# Logger_ver1_0_0.net
KiCad netlist of a schematic drawn in EAGLE
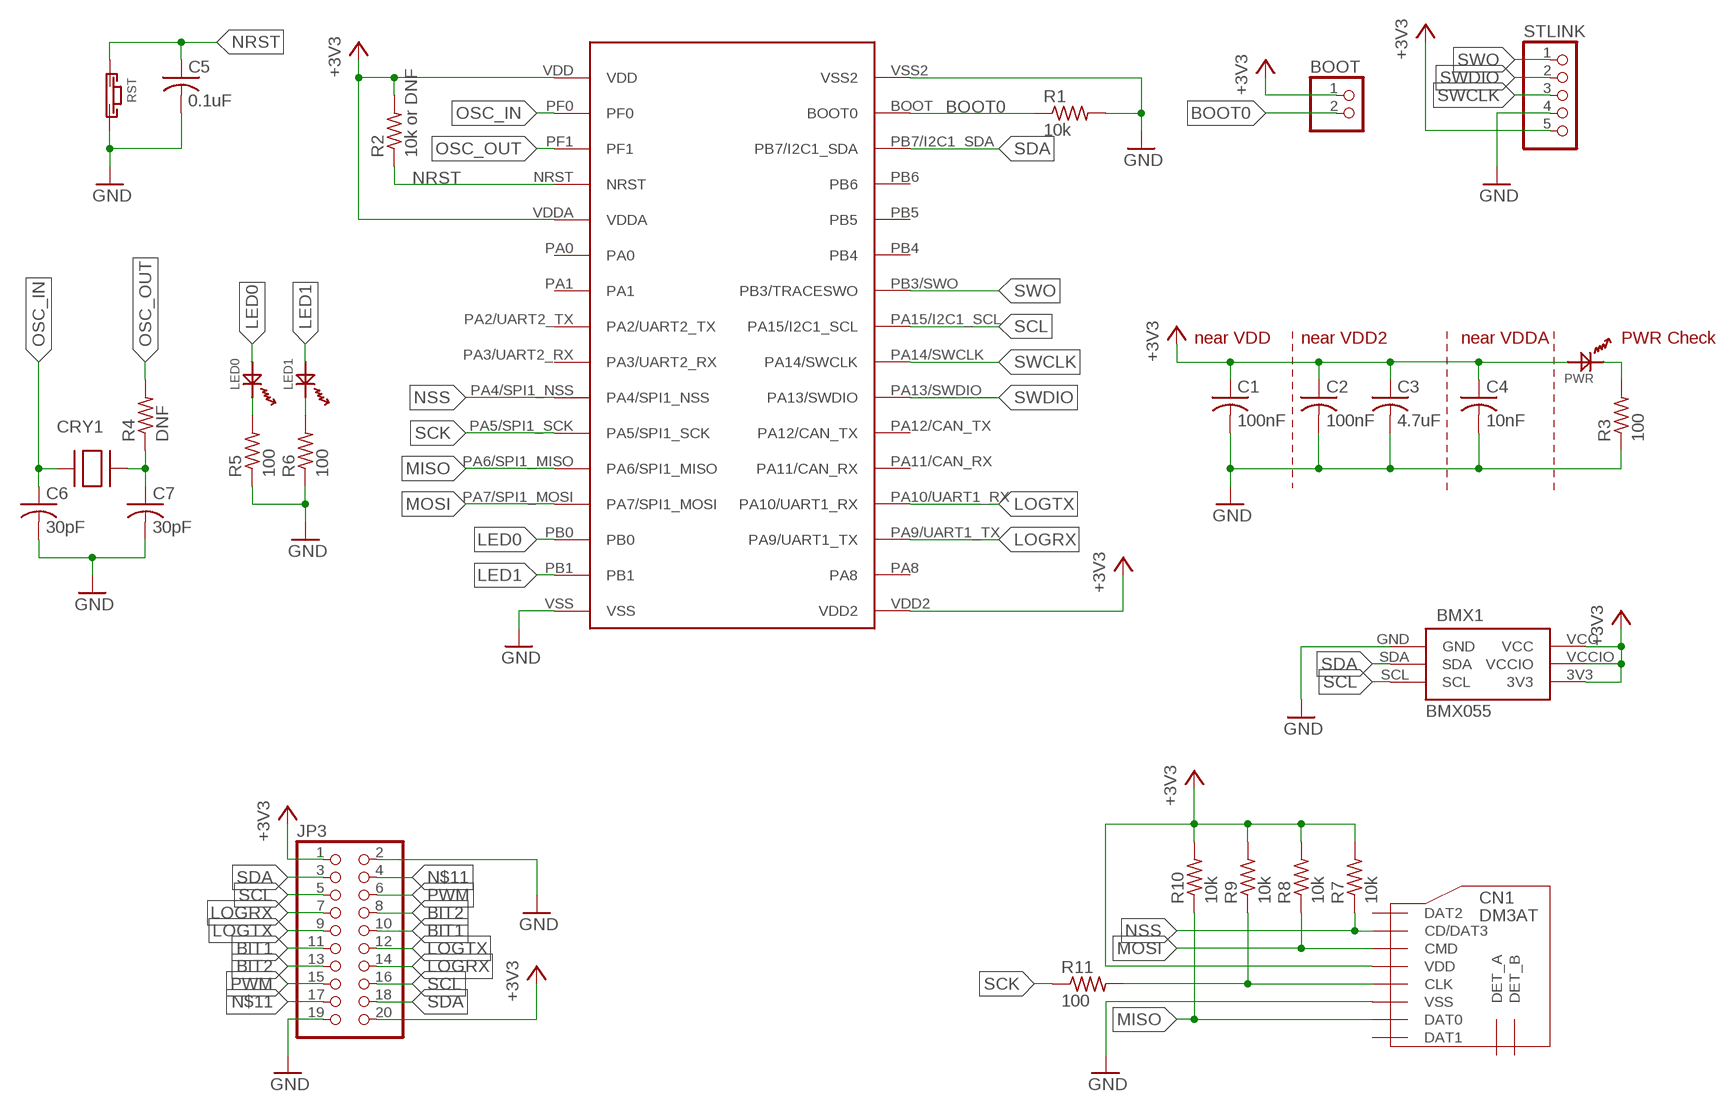
[diagram p0: schematic, sheet 1]

(export (version "E")
  (design (tool "Eeschema 10.0.6"))
  (components
    (comp (ref "BMX1")
      (value "BMX055")
      (footprint "eagle-import:BMX055")
      (libsource (lib "eagle-import") (part "BMX055"))
    )
    (comp (ref "BOOT")
      (value "PINHD-1X2/90")
      (footprint "eagle-import:1X02_90")
      (libsource (lib "eagle-import") (part "PINHD-1X2/90"))
    )
    (comp (ref "C1")
      (value "100nF")
      (footprint "eagle-import:C1608")
      (libsource (lib "eagle-import") (part "C-USC1608"))
    )
    (comp (ref "C2")
      (value "100nF")
      (footprint "eagle-import:C1608")
      (libsource (lib "eagle-import") (part "C-USC1608"))
    )
    (comp (ref "C3")
      (value "4.7uF")
      (footprint "eagle-import:C1608")
      (libsource (lib "eagle-import") (part "C-USC1608"))
    )
    (comp (ref "C4")
      (value "10nF")
      (footprint "eagle-import:C1608")
      (libsource (lib "eagle-import") (part "C-USC1608"))
    )
    (comp (ref "C5")
      (value "0.1uF")
      (footprint "eagle-import:C1608")
      (libsource (lib "eagle-import") (part "C-USC1608"))
    )
    (comp (ref "C6")
      (value "30pF")
      (footprint "eagle-import:C1608")
      (libsource (lib "eagle-import") (part "C-USC1608"))
    )
    (comp (ref "C7")
      (value "30pF")
      (footprint "eagle-import:C1608")
      (libsource (lib "eagle-import") (part "C-USC1608"))
    )
    (comp (ref "CN1")
      (value "DM3AT")
      (footprint "eagle-import:DM3AT")
      (libsource (lib "eagle-import") (part "DM3AT"))
    )
    (comp (ref "CRY1")
      (value "8MHZ")
      (footprint "eagle-import:CRYSTAL")
      (libsource (lib "eagle-import") (part "8MHZ"))
    )
    (comp (ref "JP3")
      (value "PINHD-2X10/90")
      (footprint "eagle-import:2X10_90")
      (libsource (lib "eagle-import") (part "PINHD-2X10/90"))
    )
    (comp (ref "LED0")
      (value "OSXX1608C1A")
      (footprint "eagle-import:OSXX1608C1A")
      (libsource (lib "eagle-import") (part "OSXX1608C1A"))
    )
    (comp (ref "LED1")
      (value "OSXX1608C1A")
      (footprint "eagle-import:OSXX1608C1A")
      (libsource (lib "eagle-import") (part "OSXX1608C1A"))
    )
    (comp (ref "PWR")
      (value "OSXX1608C1A")
      (footprint "eagle-import:OSXX1608C1A")
      (libsource (lib "eagle-import") (part "OSXX1608C1A"))
    )
    (comp (ref "R1")
      (value "10k")
      (footprint "eagle-import:R0603")
      (libsource (lib "eagle-import") (part "R-US_R0603"))
    )
    (comp (ref "R2")
      (value "10k or DNF")
      (footprint "eagle-import:R0603")
      (libsource (lib "eagle-import") (part "R-US_R0603"))
    )
    (comp (ref "R3")
      (value "100")
      (footprint "eagle-import:R0603")
      (libsource (lib "eagle-import") (part "R-US_R0603"))
    )
    (comp (ref "R4")
      (value "DNF")
      (footprint "eagle-import:R0603")
      (libsource (lib "eagle-import") (part "R-US_R0603"))
    )
    (comp (ref "R5")
      (value "100")
      (footprint "eagle-import:R0603")
      (libsource (lib "eagle-import") (part "R-US_R0603"))
    )
    (comp (ref "R6")
      (value "100")
      (footprint "eagle-import:R0603")
      (libsource (lib "eagle-import") (part "R-US_R0603"))
    )
    (comp (ref "R7")
      (value "10k")
      (footprint "eagle-import:R0603")
      (libsource (lib "eagle-import") (part "R-US_R0603"))
    )
    (comp (ref "R8")
      (value "10k")
      (footprint "eagle-import:R0603")
      (libsource (lib "eagle-import") (part "R-US_R0603"))
    )
    (comp (ref "R9")
      (value "10k")
      (footprint "eagle-import:R0603")
      (libsource (lib "eagle-import") (part "R-US_R0603"))
    )
    (comp (ref "R10")
      (value "10k")
      (footprint "eagle-import:R0603")
      (libsource (lib "eagle-import") (part "R-US_R0603"))
    )
    (comp (ref "R11")
      (value "100")
      (footprint "eagle-import:R0603")
      (libsource (lib "eagle-import") (part "R-US_R0603"))
    )
    (comp (ref "RST")
      (value "TVAF06-A020B-R")
      (footprint "eagle-import:TVAF06-A020B-R")
      (libsource (lib "eagle-import") (part "TVAF06-A020B-R"))
    )
    (comp (ref "STLINK")
      (value "PINHD-1X5/90")
      (footprint "eagle-import:1X05_90")
      (libsource (lib "eagle-import") (part "PINHD-1X5/90"))
    )
    (comp (ref "U$1")
      (value "STM32F303K8")
      (footprint "eagle-import:STM32F303K8")
      (libsource (lib "eagle-import") (part "STM32F303K8"))
    )
  )
  (nets
    (net (code "1") (name "+3V3") (class "Default")
      (node (ref "BMX1") (pin "3V3") (pinfunction "3V3_3V3") (pintype "power_in"))
      (node (ref "BMX1") (pin "VCC") (pinfunction "VCC_VCC") (pintype "power_in"))
      (node (ref "BMX1") (pin "VCCIO") (pinfunction "VCCIO_VCCIO") (pintype "power_in"))
      (node (ref "BOOT") (pin "1") (pinfunction "1_1") (pintype "passive"))
      (node (ref "C1") (pin "1") (pinfunction "1_1") (pintype "passive"))
      (node (ref "C2") (pin "1") (pinfunction "1_1") (pintype "passive"))
      (node (ref "C3") (pin "1") (pinfunction "1_1") (pintype "passive"))
      (node (ref "C4") (pin "1") (pinfunction "1_1") (pintype "passive"))
      (node (ref "CN1") (pin "VDD") (pinfunction "VDD_VDD") (pintype "bidirectional"))
      (node (ref "JP3") (pin "1") (pinfunction "1_1") (pintype "passive"))
      (node (ref "JP3") (pin "20") (pinfunction "20_20") (pintype "passive"))
      (node (ref "PWR") (pin "AN") (pinfunction "AN_AN") (pintype "bidirectional"))
      (node (ref "R10") (pin "2") (pinfunction "2_2") (pintype "passive"))
      (node (ref "R2") (pin "2") (pinfunction "2_2") (pintype "passive"))
      (node (ref "R7") (pin "2") (pinfunction "2_2") (pintype "passive"))
      (node (ref "R8") (pin "2") (pinfunction "2_2") (pintype "passive"))
      (node (ref "R9") (pin "2") (pinfunction "2_2") (pintype "passive"))
      (node (ref "STLINK") (pin "5") (pinfunction "5_5") (pintype "passive"))
      (node (ref "U$1") (pin "VDD") (pinfunction "VDD_VDD") (pintype "power_in"))
      (node (ref "U$1") (pin "VDD2") (pinfunction "VDD2_VDD2") (pintype "power_in"))
      (node (ref "U$1") (pin "VDDA") (pinfunction "VDDA_VDDA") (pintype "power_in"))
    )
    (net (code "2") (name "BIT1") (class "Default")
      (node (ref "JP3") (pin "10") (pinfunction "10_10") (pintype "passive"))
      (node (ref "JP3") (pin "11") (pinfunction "11_11") (pintype "passive"))
    )
    (net (code "3") (name "BIT2") (class "Default")
      (node (ref "JP3") (pin "13") (pinfunction "13_13") (pintype "passive"))
      (node (ref "JP3") (pin "8") (pinfunction "8_8") (pintype "passive"))
    )
    (net (code "4") (name "BOOT0") (class "Default")
      (node (ref "BOOT") (pin "2") (pinfunction "2_2") (pintype "passive"))
      (node (ref "R1") (pin "1") (pinfunction "1_1") (pintype "passive"))
      (node (ref "U$1") (pin "BOOT") (pinfunction "BOOT0_BOOT") (pintype "bidirectional"))
    )
    (net (code "5") (name "GND") (class "Default")
      (node (ref "BMX1") (pin "GND") (pinfunction "GND_GND") (pintype "power_in"))
      (node (ref "C1") (pin "2") (pinfunction "2_2") (pintype "passive"))
      (node (ref "C2") (pin "2") (pinfunction "2_2") (pintype "passive"))
      (node (ref "C3") (pin "2") (pinfunction "2_2") (pintype "passive"))
      (node (ref "C4") (pin "2") (pinfunction "2_2") (pintype "passive"))
      (node (ref "C5") (pin "2") (pinfunction "2_2") (pintype "passive"))
      (node (ref "C6") (pin "2") (pinfunction "2_2") (pintype "passive"))
      (node (ref "C7") (pin "2") (pinfunction "2_2") (pintype "passive"))
      (node (ref "CN1") (pin "VSS") (pinfunction "VSS_VSS") (pintype "bidirectional"))
      (node (ref "JP3") (pin "19") (pinfunction "19_19") (pintype "passive"))
      (node (ref "JP3") (pin "2") (pinfunction "2_2") (pintype "passive"))
      (node (ref "R1") (pin "2") (pinfunction "2_2") (pintype "passive"))
      (node (ref "R3") (pin "1") (pinfunction "1_1") (pintype "passive"))
      (node (ref "R5") (pin "1") (pinfunction "1_1") (pintype "passive"))
      (node (ref "R6") (pin "1") (pinfunction "1_1") (pintype "passive"))
      (node (ref "RST") (pin "P$2") (pinfunction "P$2_P$2") (pintype "bidirectional"))
      (node (ref "STLINK") (pin "4") (pinfunction "4_4") (pintype "passive"))
      (node (ref "U$1") (pin "VSS") (pinfunction "VSS_VSS") (pintype "power_in"))
      (node (ref "U$1") (pin "VSS2") (pinfunction "VSS2_VSS2") (pintype "power_in"))
    )
    (net (code "6") (name "LED0") (class "Default")
      (node (ref "LED0") (pin "AN") (pinfunction "AN_AN") (pintype "bidirectional"))
      (node (ref "U$1") (pin "PB0") (pinfunction "PB0_PB0") (pintype "bidirectional"))
    )
    (net (code "7") (name "LED1") (class "Default")
      (node (ref "LED1") (pin "AN") (pinfunction "AN_AN") (pintype "bidirectional"))
      (node (ref "U$1") (pin "PB1") (pinfunction "PB1_PB1") (pintype "bidirectional"))
    )
    (net (code "8") (name "LOGRX") (class "Default")
      (node (ref "JP3") (pin "14") (pinfunction "14_14") (pintype "passive"))
      (node (ref "JP3") (pin "7") (pinfunction "7_7") (pintype "passive"))
      (node (ref "U$1") (pin "PA9/UART1_TX") (pinfunction "PA9/UART1_TX_PA9/UART1_TX") (pintype "bidirectional"))
    )
    (net (code "9") (name "LOGTX") (class "Default")
      (node (ref "JP3") (pin "12") (pinfunction "12_12") (pintype "passive"))
      (node (ref "JP3") (pin "9") (pinfunction "9_9") (pintype "passive"))
      (node (ref "U$1") (pin "PA10/UART1_RX") (pinfunction "PA10/UART1_RX_PA10/UART1_RX") (pintype "bidirectional"))
    )
    (net (code "10") (name "MISO") (class "Default")
      (node (ref "CN1") (pin "DAT0") (pinfunction "DAT0_DAT0") (pintype "bidirectional"))
      (node (ref "R10") (pin "1") (pinfunction "1_1") (pintype "passive"))
      (node (ref "U$1") (pin "PA6/SPI1_MISO") (pinfunction "PA6/SPI1_MISO_PA6/SPI1_MISO") (pintype "bidirectional"))
    )
    (net (code "11") (name "MOSI") (class "Default")
      (node (ref "CN1") (pin "CMD") (pinfunction "CMD_CMD") (pintype "bidirectional"))
      (node (ref "R8") (pin "1") (pinfunction "1_1") (pintype "passive"))
      (node (ref "U$1") (pin "PA7/SPI1_MOSI") (pinfunction "PA7/SPI1_MOSI_PA7/SPI1_MOSI") (pintype "bidirectional"))
    )
    (net (code "12") (name "N$11") (class "Default")
      (node (ref "JP3") (pin "17") (pinfunction "17_17") (pintype "passive"))
      (node (ref "JP3") (pin "4") (pinfunction "4_4") (pintype "passive"))
    )
    (net (code "13") (name "NRST") (class "Default")
      (node (ref "C5") (pin "1") (pinfunction "1_1") (pintype "passive"))
      (node (ref "R2") (pin "1") (pinfunction "1_1") (pintype "passive"))
      (node (ref "RST") (pin "P$1") (pinfunction "P$1_P$1") (pintype "bidirectional"))
      (node (ref "U$1") (pin "NRST") (pinfunction "NRST_NRST") (pintype "bidirectional"))
    )
    (net (code "14") (name "NSS") (class "Default")
      (node (ref "CN1") (pin "CD/DAT3") (pinfunction "CD/DAT3_CD/DAT3") (pintype "bidirectional"))
      (node (ref "R7") (pin "1") (pinfunction "1_1") (pintype "passive"))
      (node (ref "U$1") (pin "PA4/SPI1_NSS") (pinfunction "PA4/SPI1_NSS_PA4/SPI1_NSS") (pintype "bidirectional"))
    )
    (net (code "15") (name "Net-(C7-Pad1)") (class "Default")
      (node (ref "C7") (pin "1") (pinfunction "1_1") (pintype "passive"))
      (node (ref "CRY1") (pin "P$2") (pinfunction "P$2_P$2") (pintype "bidirectional"))
      (node (ref "R4") (pin "1") (pinfunction "1_1") (pintype "passive"))
    )
    (net (code "16") (name "Net-(CN1-PadCLK)") (class "Default")
      (node (ref "CN1") (pin "CLK") (pinfunction "CLK_CLK") (pintype "bidirectional"))
      (node (ref "R11") (pin "2") (pinfunction "2_2") (pintype "passive"))
      (node (ref "R9") (pin "1") (pinfunction "1_1") (pintype "passive"))
    )
    (net (code "17") (name "Net-(LED0-PadCT)") (class "Default")
      (node (ref "LED0") (pin "CT") (pinfunction "CT_CT") (pintype "bidirectional"))
      (node (ref "R5") (pin "2") (pinfunction "2_2") (pintype "passive"))
    )
    (net (code "18") (name "Net-(LED1-PadCT)") (class "Default")
      (node (ref "LED1") (pin "CT") (pinfunction "CT_CT") (pintype "bidirectional"))
      (node (ref "R6") (pin "2") (pinfunction "2_2") (pintype "passive"))
    )
    (net (code "19") (name "Net-(PWR-PadCT)") (class "Default")
      (node (ref "PWR") (pin "CT") (pinfunction "CT_CT") (pintype "bidirectional"))
      (node (ref "R3") (pin "2") (pinfunction "2_2") (pintype "passive"))
    )
    (net (code "20") (name "OSC_IN") (class "Default")
      (node (ref "C6") (pin "1") (pinfunction "1_1") (pintype "passive"))
      (node (ref "CRY1") (pin "P$1") (pinfunction "P$1_P$1") (pintype "bidirectional"))
      (node (ref "U$1") (pin "PF0") (pinfunction "PF0_PF0") (pintype "bidirectional"))
    )
    (net (code "21") (name "OSC_OUT") (class "Default")
      (node (ref "R4") (pin "2") (pinfunction "2_2") (pintype "passive"))
      (node (ref "U$1") (pin "PF1") (pinfunction "PF1_PF1") (pintype "bidirectional"))
    )
    (net (code "22") (name "PWM") (class "Default")
      (node (ref "JP3") (pin "15") (pinfunction "15_15") (pintype "passive"))
      (node (ref "JP3") (pin "6") (pinfunction "6_6") (pintype "passive"))
    )
    (net (code "23") (name "SCK") (class "Default")
      (node (ref "R11") (pin "1") (pinfunction "1_1") (pintype "passive"))
      (node (ref "U$1") (pin "PA5/SPI1_SCK") (pinfunction "PA5/SPI1_SCK_PA5/SPI1_SCK") (pintype "bidirectional"))
    )
    (net (code "24") (name "SCL") (class "Default")
      (node (ref "BMX1") (pin "SCL") (pinfunction "SCL_SCL") (pintype "bidirectional"))
      (node (ref "JP3") (pin "16") (pinfunction "16_16") (pintype "passive"))
      (node (ref "JP3") (pin "5") (pinfunction "5_5") (pintype "passive"))
      (node (ref "U$1") (pin "PA15/I2C1_SCL") (pinfunction "PA15/I2C1_SCL_PA15/I2C1_SCL") (pintype "bidirectional"))
    )
    (net (code "25") (name "SDA") (class "Default")
      (node (ref "BMX1") (pin "SDA") (pinfunction "SDA_SDA") (pintype "bidirectional"))
      (node (ref "JP3") (pin "18") (pinfunction "18_18") (pintype "passive"))
      (node (ref "JP3") (pin "3") (pinfunction "3_3") (pintype "passive"))
      (node (ref "U$1") (pin "PB7/I2C1_SDA") (pinfunction "PB7/I2C1_SDA_PB7/I2C1_SDA") (pintype "bidirectional"))
    )
    (net (code "26") (name "SWCLK") (class "Default")
      (node (ref "STLINK") (pin "3") (pinfunction "3_3") (pintype "passive"))
      (node (ref "U$1") (pin "PA14/SWCLK") (pinfunction "PA14/SWCLK_PA14/SWCLK") (pintype "bidirectional"))
    )
    (net (code "27") (name "SWDIO") (class "Default")
      (node (ref "STLINK") (pin "2") (pinfunction "2_2") (pintype "passive"))
      (node (ref "U$1") (pin "PA13/SWDIO") (pinfunction "PA13/SWDIO_PA13/SWDIO") (pintype "bidirectional"))
    )
    (net (code "28") (name "SWO") (class "Default")
      (node (ref "STLINK") (pin "1") (pinfunction "1_1") (pintype "passive"))
      (node (ref "U$1") (pin "PB3/SWO") (pinfunction "PB3/TRACESWO_PB3/SWO") (pintype "bidirectional"))
    )
    (net (code "29") (name "unconnected-(CN1-PadDAT1)") (class "Default")
      (node (ref "CN1") (pin "DAT1") (pinfunction "DAT1_DAT1") (pintype "bidirectional"))
    )
    (net (code "30") (name "unconnected-(CN1-PadDAT2)") (class "Default")
      (node (ref "CN1") (pin "DAT2") (pinfunction "DAT2_DAT2") (pintype "bidirectional"))
    )
    (net (code "31") (name "unconnected-(CN1-PadDET_A)") (class "Default")
      (node (ref "CN1") (pin "DET_A") (pinfunction "DET_A_DET_A") (pintype "bidirectional"))
    )
    (net (code "32") (name "unconnected-(CN1-PadDET_B)") (class "Default")
      (node (ref "CN1") (pin "DET_B") (pinfunction "DET_B_DET_B") (pintype "bidirectional"))
    )
    (net (code "33") (name "unconnected-(U$1-PadPA0)") (class "Default")
      (node (ref "U$1") (pin "PA0") (pinfunction "PA0_PA0") (pintype "bidirectional"))
    )
    (net (code "34") (name "unconnected-(U$1-PadPA1)") (class "Default")
      (node (ref "U$1") (pin "PA1") (pinfunction "PA1_PA1") (pintype "bidirectional"))
    )
    (net (code "35") (name "unconnected-(U$1-PadPA2{slash}UART2_TX)") (class "Default")
      (node (ref "U$1") (pin "PA2/UART2_TX") (pinfunction "PA2/UART2_TX_PA2/UART2_TX") (pintype "bidirectional"))
    )
    (net (code "36") (name "unconnected-(U$1-PadPA3{slash}UART2_RX)") (class "Default")
      (node (ref "U$1") (pin "PA3/UART2_RX") (pinfunction "PA3/UART2_RX_PA3/UART2_RX") (pintype "bidirectional"))
    )
    (net (code "37") (name "unconnected-(U$1-PadPA8)") (class "Default")
      (node (ref "U$1") (pin "PA8") (pinfunction "PA8_PA8") (pintype "bidirectional"))
    )
    (net (code "38") (name "unconnected-(U$1-PadPA11{slash}CAN_RX)") (class "Default")
      (node (ref "U$1") (pin "PA11/CAN_RX") (pinfunction "PA11/CAN_RX_PA11/CAN_RX") (pintype "bidirectional"))
    )
    (net (code "39") (name "unconnected-(U$1-PadPA12{slash}CAN_TX)") (class "Default")
      (node (ref "U$1") (pin "PA12/CAN_TX") (pinfunction "PA12/CAN_TX_PA12/CAN_TX") (pintype "bidirectional"))
    )
    (net (code "40") (name "unconnected-(U$1-PadPB4)") (class "Default")
      (node (ref "U$1") (pin "PB4") (pinfunction "PB4_PB4") (pintype "bidirectional"))
    )
    (net (code "41") (name "unconnected-(U$1-PadPB5)") (class "Default")
      (node (ref "U$1") (pin "PB5") (pinfunction "PB5_PB5") (pintype "bidirectional"))
    )
    (net (code "42") (name "unconnected-(U$1-PadPB6)") (class "Default")
      (node (ref "U$1") (pin "PB6") (pinfunction "PB6_PB6") (pintype "bidirectional"))
    )
  )
)
